# Brakeout_board_-_wire_connection.net
KiCad netlist of a schematic drawn in EAGLE
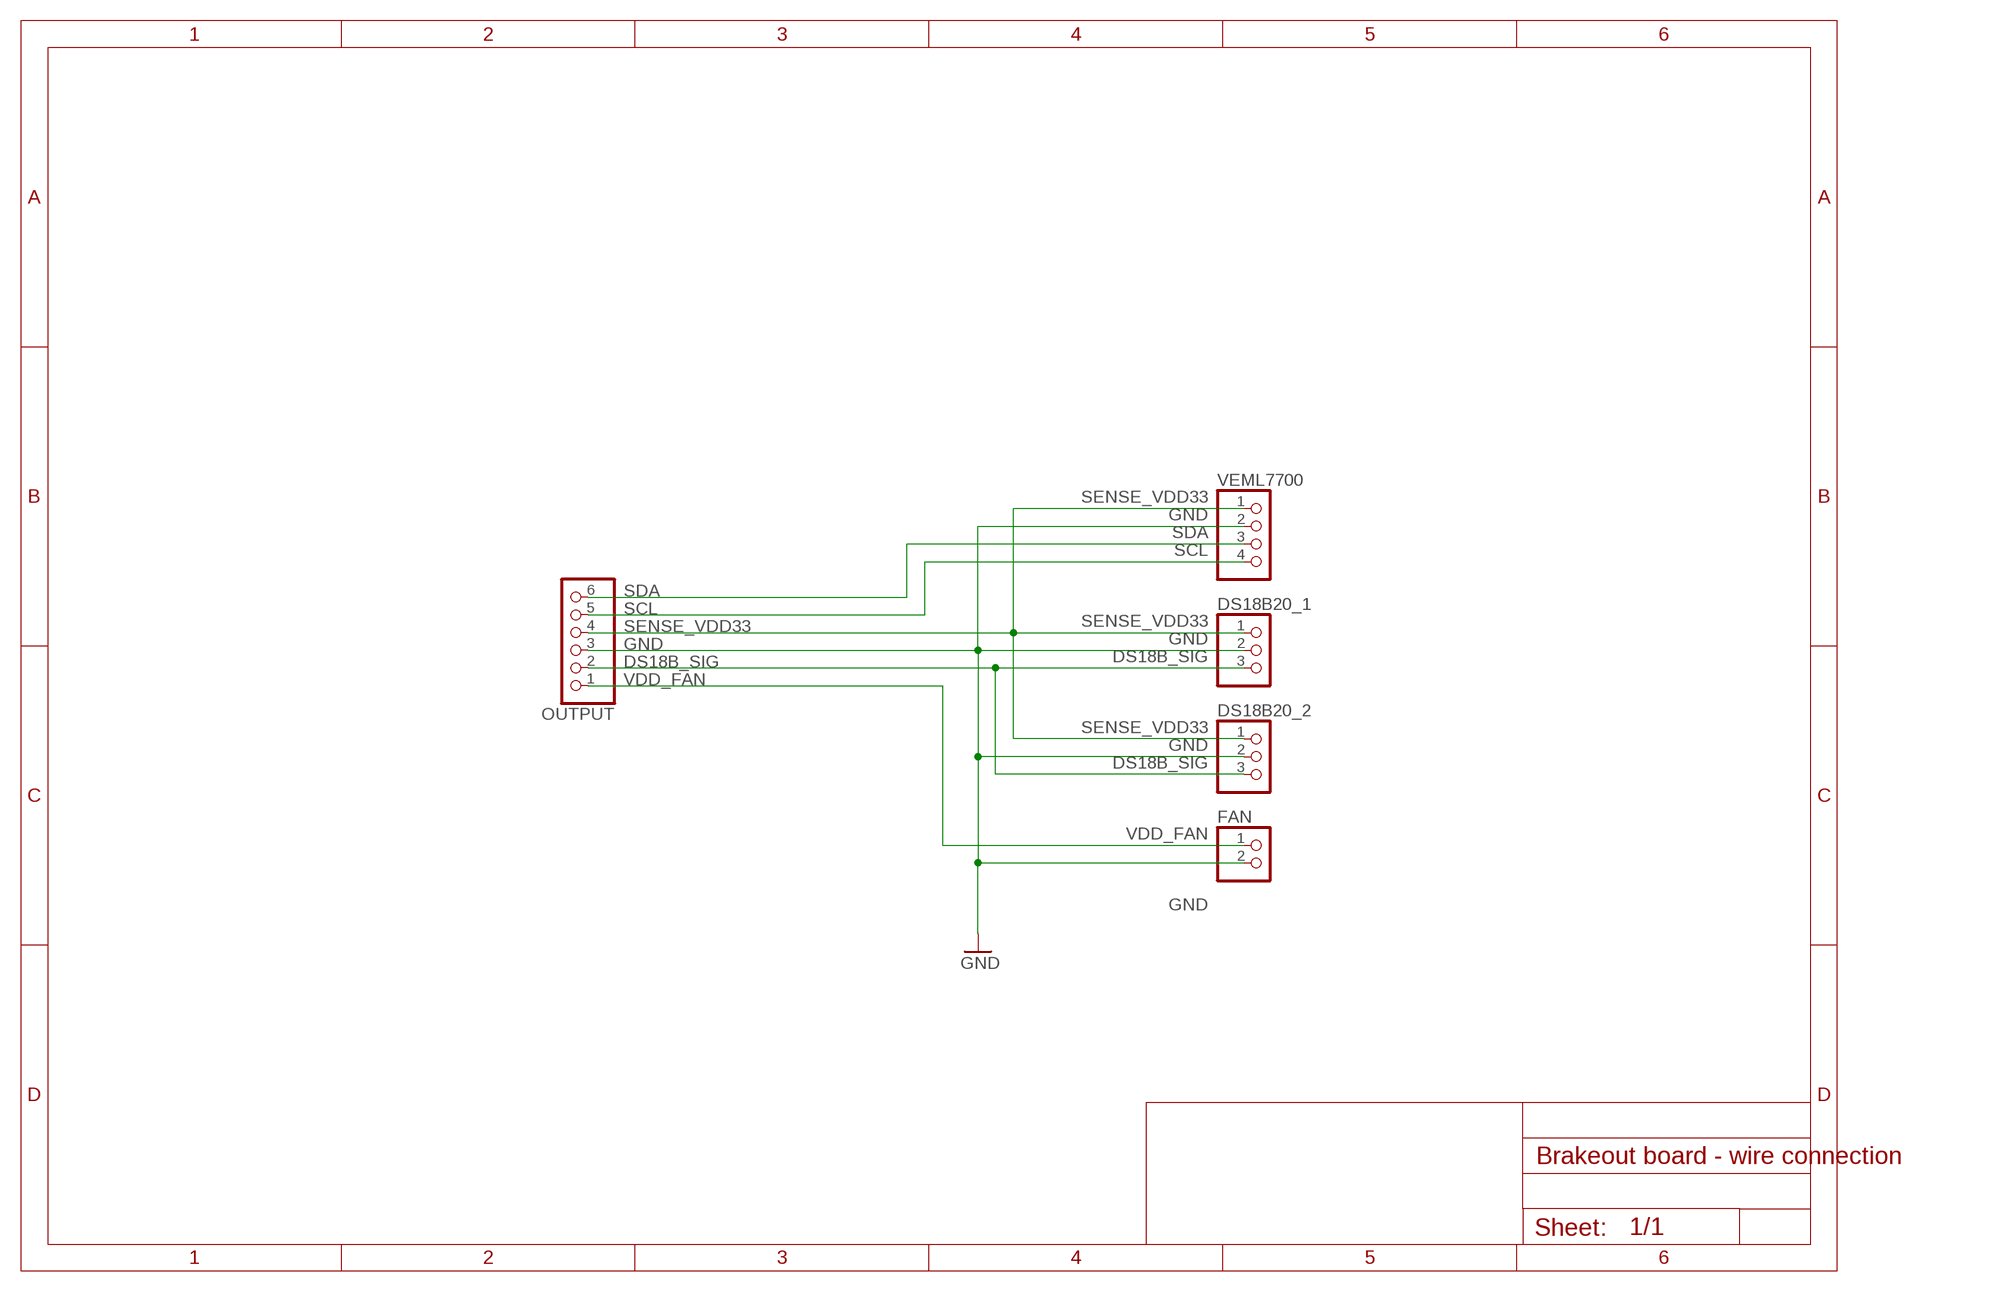
[diagram p0: schematic, sheet 1]

(export (version "E")
  (design (tool "Eeschema 10.0.6"))
  (components
    (comp (ref "DS18B20_1")
      (value "PINHD-1X3")
      (footprint "eagle-import:1X03")
      (libsource (lib "eagle-import") (part "PINHD-1X3"))
    )
    (comp (ref "DS18B20_2")
      (value "PINHD-1X3")
      (footprint "eagle-import:1X03")
      (libsource (lib "eagle-import") (part "PINHD-1X3"))
    )
    (comp (ref "FAN")
      (value "PINHD-1X2")
      (footprint "eagle-import:1X02")
      (libsource (lib "eagle-import") (part "PINHD-1X2"))
    )
    (comp (ref "OUTPUT")
      (value "PINHD-1X6")
      (footprint "eagle-import:1X06")
      (libsource (lib "eagle-import") (part "PINHD-1X6"))
    )
    (comp (ref "VEML7700")
      (value "PINHD-1X4")
      (footprint "eagle-import:1X04")
      (libsource (lib "eagle-import") (part "PINHD-1X4"))
    )
  )
  (nets
    (net (code "1") (name "/DS18B_SIG") (class "Default")
      (node (ref "DS18B20_1") (pin "3") (pinfunction "3_3") (pintype "passive"))
      (node (ref "DS18B20_2") (pin "3") (pinfunction "3_3") (pintype "passive"))
      (node (ref "OUTPUT") (pin "2") (pinfunction "2_2") (pintype "passive"))
    )
    (net (code "2") (name "/SCL") (class "Default")
      (node (ref "OUTPUT") (pin "5") (pinfunction "5_5") (pintype "passive"))
      (node (ref "VEML7700") (pin "4") (pinfunction "4_4") (pintype "passive"))
    )
    (net (code "3") (name "/SDA") (class "Default")
      (node (ref "OUTPUT") (pin "6") (pinfunction "6_6") (pintype "passive"))
      (node (ref "VEML7700") (pin "3") (pinfunction "3_3") (pintype "passive"))
    )
    (net (code "4") (name "/SENSE_VDD33") (class "Default")
      (node (ref "DS18B20_1") (pin "1") (pinfunction "1_1") (pintype "passive"))
      (node (ref "DS18B20_2") (pin "1") (pinfunction "1_1") (pintype "passive"))
      (node (ref "OUTPUT") (pin "4") (pinfunction "4_4") (pintype "passive"))
      (node (ref "VEML7700") (pin "1") (pinfunction "1_1") (pintype "passive"))
    )
    (net (code "5") (name "/VDD_FAN") (class "Default")
      (node (ref "FAN") (pin "1") (pinfunction "1_1") (pintype "passive"))
      (node (ref "OUTPUT") (pin "1") (pinfunction "1_1") (pintype "passive"))
    )
    (net (code "6") (name "GND") (class "Default")
      (node (ref "DS18B20_1") (pin "2") (pinfunction "2_2") (pintype "passive"))
      (node (ref "DS18B20_2") (pin "2") (pinfunction "2_2") (pintype "passive"))
      (node (ref "FAN") (pin "2") (pinfunction "2_2") (pintype "passive"))
      (node (ref "OUTPUT") (pin "3") (pinfunction "3_3") (pintype "passive"))
      (node (ref "VEML7700") (pin "2") (pinfunction "2_2") (pintype "passive"))
    )
  )
)
